# main.net
KiCad netlist of a schematic drawn in EAGLE
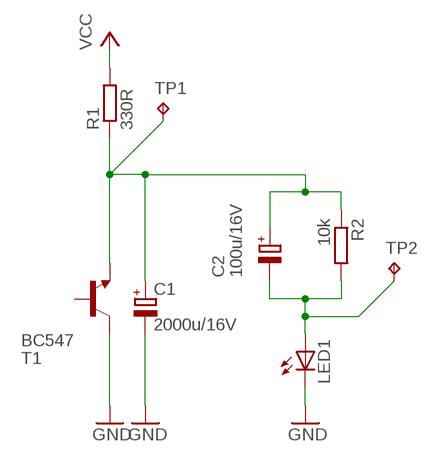
[diagram p0: schematic, sheet 1]

(export (version "E")
  (design (tool "Eeschema 10.0.6"))
  (components
    (comp (ref "C1")
      (value "2000u/16V")
      (footprint "eagle-import:085CS_1AR")
      (libsource (lib "eagle-import") (part "CPOL-EU085CS-1AR"))
    )
    (comp (ref "C2")
      (value "100u/16V")
      (footprint "eagle-import:085CS_1AR")
      (libsource (lib "eagle-import") (part "CPOL-EU085CS-1AR"))
    )
    (comp (ref "LED1")
      (value "LEDB152")
      (footprint "eagle-import:Q62902-B152")
      (libsource (lib "eagle-import") (part "LEDB152"))
    )
    (comp (ref "R1")
      (value "330R")
      (footprint "eagle-import:0204_5")
      (libsource (lib "eagle-import") (part "R-EU_0204/5"))
    )
    (comp (ref "R2")
      (value "10k")
      (footprint "eagle-import:0204_5")
      (libsource (lib "eagle-import") (part "R-EU_0204/5"))
    )
    (comp (ref "T1")
      (value "BC547")
      (footprint "eagle-import:TO92")
      (libsource (lib "eagle-import") (part "BC547"))
    )
    (comp (ref "TP1")
      (value "TPTP11SQ")
      (footprint "eagle-import:TP11SQ")
      (libsource (lib "eagle-import") (part "TPTP11SQ"))
    )
    (comp (ref "TP2")
      (value "TPTP11SQ")
      (footprint "eagle-import:TP11SQ")
      (libsource (lib "eagle-import") (part "TPTP11SQ"))
    )
  )
  (nets
    (net (code "1") (name "GND") (class "Default")
      (node (ref "C1") (pin "-") (pinfunction "-_-") (pintype "passive"))
      (node (ref "LED1") (pin "K") (pinfunction "C_K") (pintype "passive"))
      (node (ref "T1") (pin "3") (pinfunction "C_3") (pintype "passive"))
    )
    (net (code "2") (name "Net-(C2-Pad-)") (class "Default")
      (node (ref "C2") (pin "-") (pinfunction "-_-") (pintype "passive"))
      (node (ref "LED1") (pin "A") (pinfunction "A_A") (pintype "passive"))
      (node (ref "R2") (pin "2") (pinfunction "2_2") (pintype "passive"))
      (node (ref "TP2") (pin "TP") (pinfunction "TP_TP") (pintype "input"))
    )
    (net (code "3") (name "Net-(T1-E)") (class "Default")
      (node (ref "C1") (pin "+") (pinfunction "+_+") (pintype "passive"))
      (node (ref "C2") (pin "+") (pinfunction "+_+") (pintype "passive"))
      (node (ref "R1") (pin "1") (pinfunction "1_1") (pintype "passive"))
      (node (ref "R2") (pin "1") (pinfunction "1_1") (pintype "passive"))
      (node (ref "T1") (pin "1") (pinfunction "E_1") (pintype "passive"))
      (node (ref "TP1") (pin "TP") (pinfunction "TP_TP") (pintype "input"))
    )
    (net (code "4") (name "VCC") (class "Default")
      (node (ref "R1") (pin "2") (pinfunction "2_2") (pintype "passive"))
    )
    (net (code "5") (name "unconnected-(T1-B-Pad2)") (class "Default")
      (node (ref "T1") (pin "2") (pinfunction "B_2") (pintype "passive"))
    )
  )
)
